# TuoZhanBan_v2_0.net
KiCad netlist of a schematic drawn in EasyEDA Pro
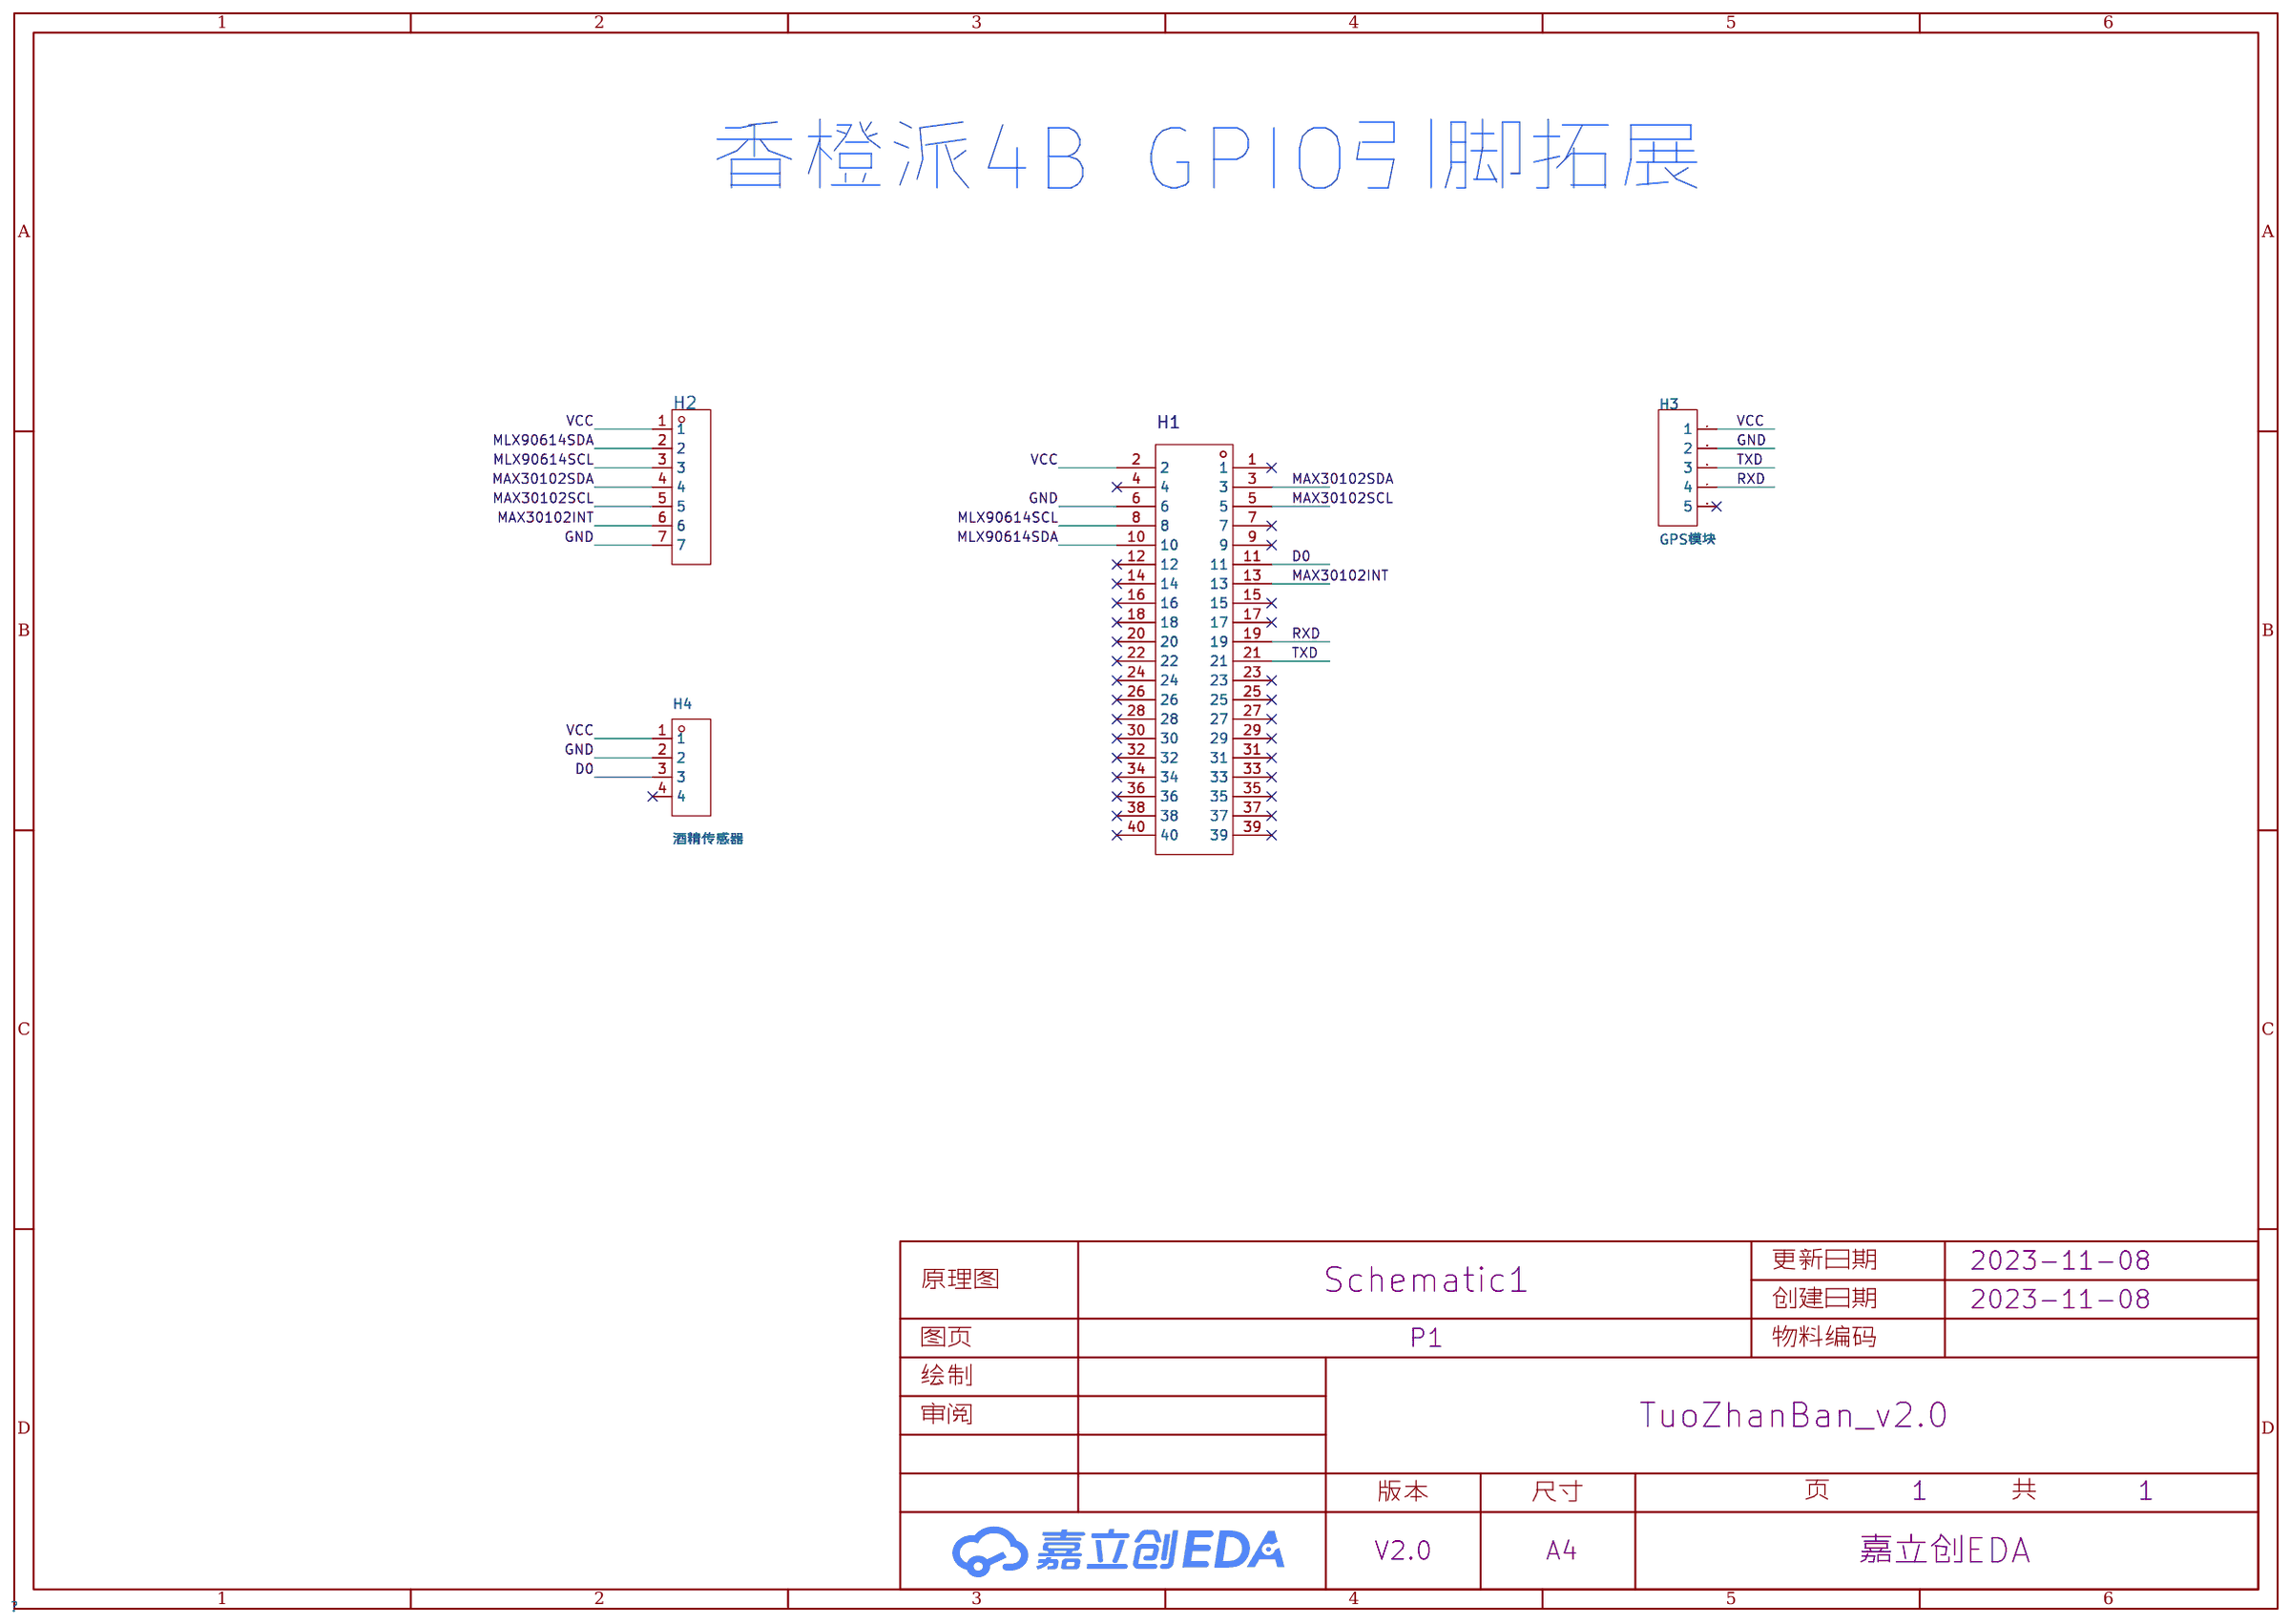
[diagram p0: schematic sheet]

(export (version "E")
  (design (tool "Eeschema 10.0.6"))
  (components
    (comp (ref "H1")
      (value "B-2100S40P-B110")
      (footprint "easyedapro:HDR-TH_40P-P2.54-V-M-R2-C20-S2.54")
      (fields (field (name "Manufacturer") "Ckmtw(灿科盟)"))
      (libsource (lib "easyedapro") (part "210S-2*20P L=11.6MMGold-plated black"))
    )
    (comp (ref "H2")
      (value "PZ254V-11-07P")
      (footprint "easyedapro:HDR-TH_7P-P2.54-V-M")
      (fields (field (name "Manufacturer") "XFCN(兴飞)"))
      (libsource (lib "easyedapro") (part "PZ254V-11-07P"))
    )
    (comp (ref "H3")
      (value "GPS模块")
      (footprint "easyedapro:HDR-TH_5P-P2.54-V-F")
      (description "排数:单排;总孔位数:5P;间距:2.54mm;插孔结构:1x5P;行距:-;安装类型:直插;塑高:-;触头材质:-;触头镀层:-;")
      (fields (field (name "Manufacturer") "BOOMELE(博穆精密)"))
      (libsource (lib "easyedapro") (part "Header-Female-2.54_1x5"))
    )
    (comp (ref "H4")
      (value "酒精传感器")
      (footprint "easyedapro:HDR-TH_4P-P2.54-V-F")
      (fields (field (name "Manufacturer") "BOOMELE(博穆精密)"))
      (libsource (lib "easyedapro") (part "2.54-1*4P母"))
    )
  )
  (nets
    (net (code "1") (name "/D0") (class "Default")
      (node (ref "H1") (pin "11") (pinfunction "11_11") (pintype "input"))
      (node (ref "H4") (pin "3") (pinfunction "3_3") (pintype "unspecified"))
    )
    (net (code "2") (name "/GND") (class "Default")
      (node (ref "H1") (pin "6") (pinfunction "6_6") (pintype "input"))
      (node (ref "H2") (pin "7") (pinfunction "7_7") (pintype "input"))
      (node (ref "H3") (pin "2") (pinfunction "2_2") (pintype "input"))
      (node (ref "H4") (pin "2") (pinfunction "2_2") (pintype "unspecified"))
    )
    (net (code "3") (name "/MAX30102INT") (class "Default")
      (node (ref "H1") (pin "13") (pinfunction "13_13") (pintype "input"))
      (node (ref "H2") (pin "6") (pinfunction "6_6") (pintype "input"))
    )
    (net (code "4") (name "/MAX30102SCL") (class "Default")
      (node (ref "H1") (pin "5") (pinfunction "5_5") (pintype "input"))
      (node (ref "H2") (pin "5") (pinfunction "5_5") (pintype "input"))
    )
    (net (code "5") (name "/MAX30102SDA") (class "Default")
      (node (ref "H1") (pin "3") (pinfunction "3_3") (pintype "input"))
      (node (ref "H2") (pin "4") (pinfunction "4_4") (pintype "input"))
    )
    (net (code "6") (name "/MLX90614SCL") (class "Default")
      (node (ref "H1") (pin "8") (pinfunction "8_8") (pintype "input"))
      (node (ref "H2") (pin "3") (pinfunction "3_3") (pintype "input"))
    )
    (net (code "7") (name "/MLX90614SDA") (class "Default")
      (node (ref "H1") (pin "10") (pinfunction "10_10") (pintype "input"))
      (node (ref "H2") (pin "2") (pinfunction "2_2") (pintype "input"))
    )
    (net (code "8") (name "/RXD") (class "Default")
      (node (ref "H1") (pin "19") (pinfunction "19_19") (pintype "input"))
      (node (ref "H3") (pin "4") (pinfunction "4_4") (pintype "input"))
    )
    (net (code "9") (name "/TXD") (class "Default")
      (node (ref "H1") (pin "21") (pinfunction "21_21") (pintype "input"))
      (node (ref "H3") (pin "3") (pinfunction "3_3") (pintype "input"))
    )
    (net (code "10") (name "/VCC") (class "Default")
      (node (ref "H1") (pin "2") (pinfunction "2_2") (pintype "input"))
      (node (ref "H2") (pin "1") (pinfunction "1_1") (pintype "input"))
      (node (ref "H3") (pin "1") (pinfunction "1_1") (pintype "input"))
      (node (ref "H4") (pin "1") (pinfunction "1_1") (pintype "unspecified"))
    )
    (net (code "11") (name "unconnected-(H1-Pad1)") (class "Default")
      (node (ref "H1") (pin "1") (pinfunction "1_1") (pintype "input+no_connect"))
    )
    (net (code "12") (name "unconnected-(H1-Pad4)") (class "Default")
      (node (ref "H1") (pin "4") (pinfunction "4_4") (pintype "input+no_connect"))
    )
    (net (code "13") (name "unconnected-(H1-Pad7)") (class "Default")
      (node (ref "H1") (pin "7") (pinfunction "7_7") (pintype "input+no_connect"))
    )
    (net (code "14") (name "unconnected-(H1-Pad9)") (class "Default")
      (node (ref "H1") (pin "9") (pinfunction "9_9") (pintype "input+no_connect"))
    )
    (net (code "15") (name "unconnected-(H1-Pad12)") (class "Default")
      (node (ref "H1") (pin "12") (pinfunction "12_12") (pintype "input+no_connect"))
    )
    (net (code "16") (name "unconnected-(H1-Pad14)") (class "Default")
      (node (ref "H1") (pin "14") (pinfunction "14_14") (pintype "input+no_connect"))
    )
    (net (code "17") (name "unconnected-(H1-Pad15)") (class "Default")
      (node (ref "H1") (pin "15") (pinfunction "15_15") (pintype "input+no_connect"))
    )
    (net (code "18") (name "unconnected-(H1-Pad16)") (class "Default")
      (node (ref "H1") (pin "16") (pinfunction "16_16") (pintype "input+no_connect"))
    )
    (net (code "19") (name "unconnected-(H1-Pad17)") (class "Default")
      (node (ref "H1") (pin "17") (pinfunction "17_17") (pintype "input+no_connect"))
    )
    (net (code "20") (name "unconnected-(H1-Pad18)") (class "Default")
      (node (ref "H1") (pin "18") (pinfunction "18_18") (pintype "input+no_connect"))
    )
    (net (code "21") (name "unconnected-(H1-Pad20)") (class "Default")
      (node (ref "H1") (pin "20") (pinfunction "20_20") (pintype "input+no_connect"))
    )
    (net (code "22") (name "unconnected-(H1-Pad22)") (class "Default")
      (node (ref "H1") (pin "22") (pinfunction "22_22") (pintype "input+no_connect"))
    )
    (net (code "23") (name "unconnected-(H1-Pad23)") (class "Default")
      (node (ref "H1") (pin "23") (pinfunction "23_23") (pintype "input+no_connect"))
    )
    (net (code "24") (name "unconnected-(H1-Pad24)") (class "Default")
      (node (ref "H1") (pin "24") (pinfunction "24_24") (pintype "input+no_connect"))
    )
    (net (code "25") (name "unconnected-(H1-Pad25)") (class "Default")
      (node (ref "H1") (pin "25") (pinfunction "25_25") (pintype "input+no_connect"))
    )
    (net (code "26") (name "unconnected-(H1-Pad26)") (class "Default")
      (node (ref "H1") (pin "26") (pinfunction "26_26") (pintype "input+no_connect"))
    )
    (net (code "27") (name "unconnected-(H1-Pad27)") (class "Default")
      (node (ref "H1") (pin "27") (pinfunction "27_27") (pintype "input+no_connect"))
    )
    (net (code "28") (name "unconnected-(H1-Pad28)") (class "Default")
      (node (ref "H1") (pin "28") (pinfunction "28_28") (pintype "input+no_connect"))
    )
    (net (code "29") (name "unconnected-(H1-Pad29)") (class "Default")
      (node (ref "H1") (pin "29") (pinfunction "29_29") (pintype "input+no_connect"))
    )
    (net (code "30") (name "unconnected-(H1-Pad30)") (class "Default")
      (node (ref "H1") (pin "30") (pinfunction "30_30") (pintype "input+no_connect"))
    )
    (net (code "31") (name "unconnected-(H1-Pad31)") (class "Default")
      (node (ref "H1") (pin "31") (pinfunction "31_31") (pintype "input+no_connect"))
    )
    (net (code "32") (name "unconnected-(H1-Pad32)") (class "Default")
      (node (ref "H1") (pin "32") (pinfunction "32_32") (pintype "input+no_connect"))
    )
    (net (code "33") (name "unconnected-(H1-Pad33)") (class "Default")
      (node (ref "H1") (pin "33") (pinfunction "33_33") (pintype "input+no_connect"))
    )
    (net (code "34") (name "unconnected-(H1-Pad34)") (class "Default")
      (node (ref "H1") (pin "34") (pinfunction "34_34") (pintype "input+no_connect"))
    )
    (net (code "35") (name "unconnected-(H1-Pad35)") (class "Default")
      (node (ref "H1") (pin "35") (pinfunction "35_35") (pintype "input+no_connect"))
    )
    (net (code "36") (name "unconnected-(H1-Pad36)") (class "Default")
      (node (ref "H1") (pin "36") (pinfunction "36_36") (pintype "input+no_connect"))
    )
    (net (code "37") (name "unconnected-(H1-Pad37)") (class "Default")
      (node (ref "H1") (pin "37") (pinfunction "37_37") (pintype "input+no_connect"))
    )
    (net (code "38") (name "unconnected-(H1-Pad38)") (class "Default")
      (node (ref "H1") (pin "38") (pinfunction "38_38") (pintype "input+no_connect"))
    )
    (net (code "39") (name "unconnected-(H1-Pad39)") (class "Default")
      (node (ref "H1") (pin "39") (pinfunction "39_39") (pintype "input+no_connect"))
    )
    (net (code "40") (name "unconnected-(H1-Pad40)") (class "Default")
      (node (ref "H1") (pin "40") (pinfunction "40_40") (pintype "input+no_connect"))
    )
    (net (code "41") (name "unconnected-(H3-Pad5)") (class "Default")
      (node (ref "H3") (pin "5") (pinfunction "5_5") (pintype "input+no_connect"))
    )
    (net (code "42") (name "unconnected-(H4-Pad4)") (class "Default")
      (node (ref "H4") (pin "4") (pinfunction "4_4") (pintype "unspecified+no_connect"))
    )
  )
)
